# DSP.net
KiCad netlist of a schematic drawn in Altium Designer
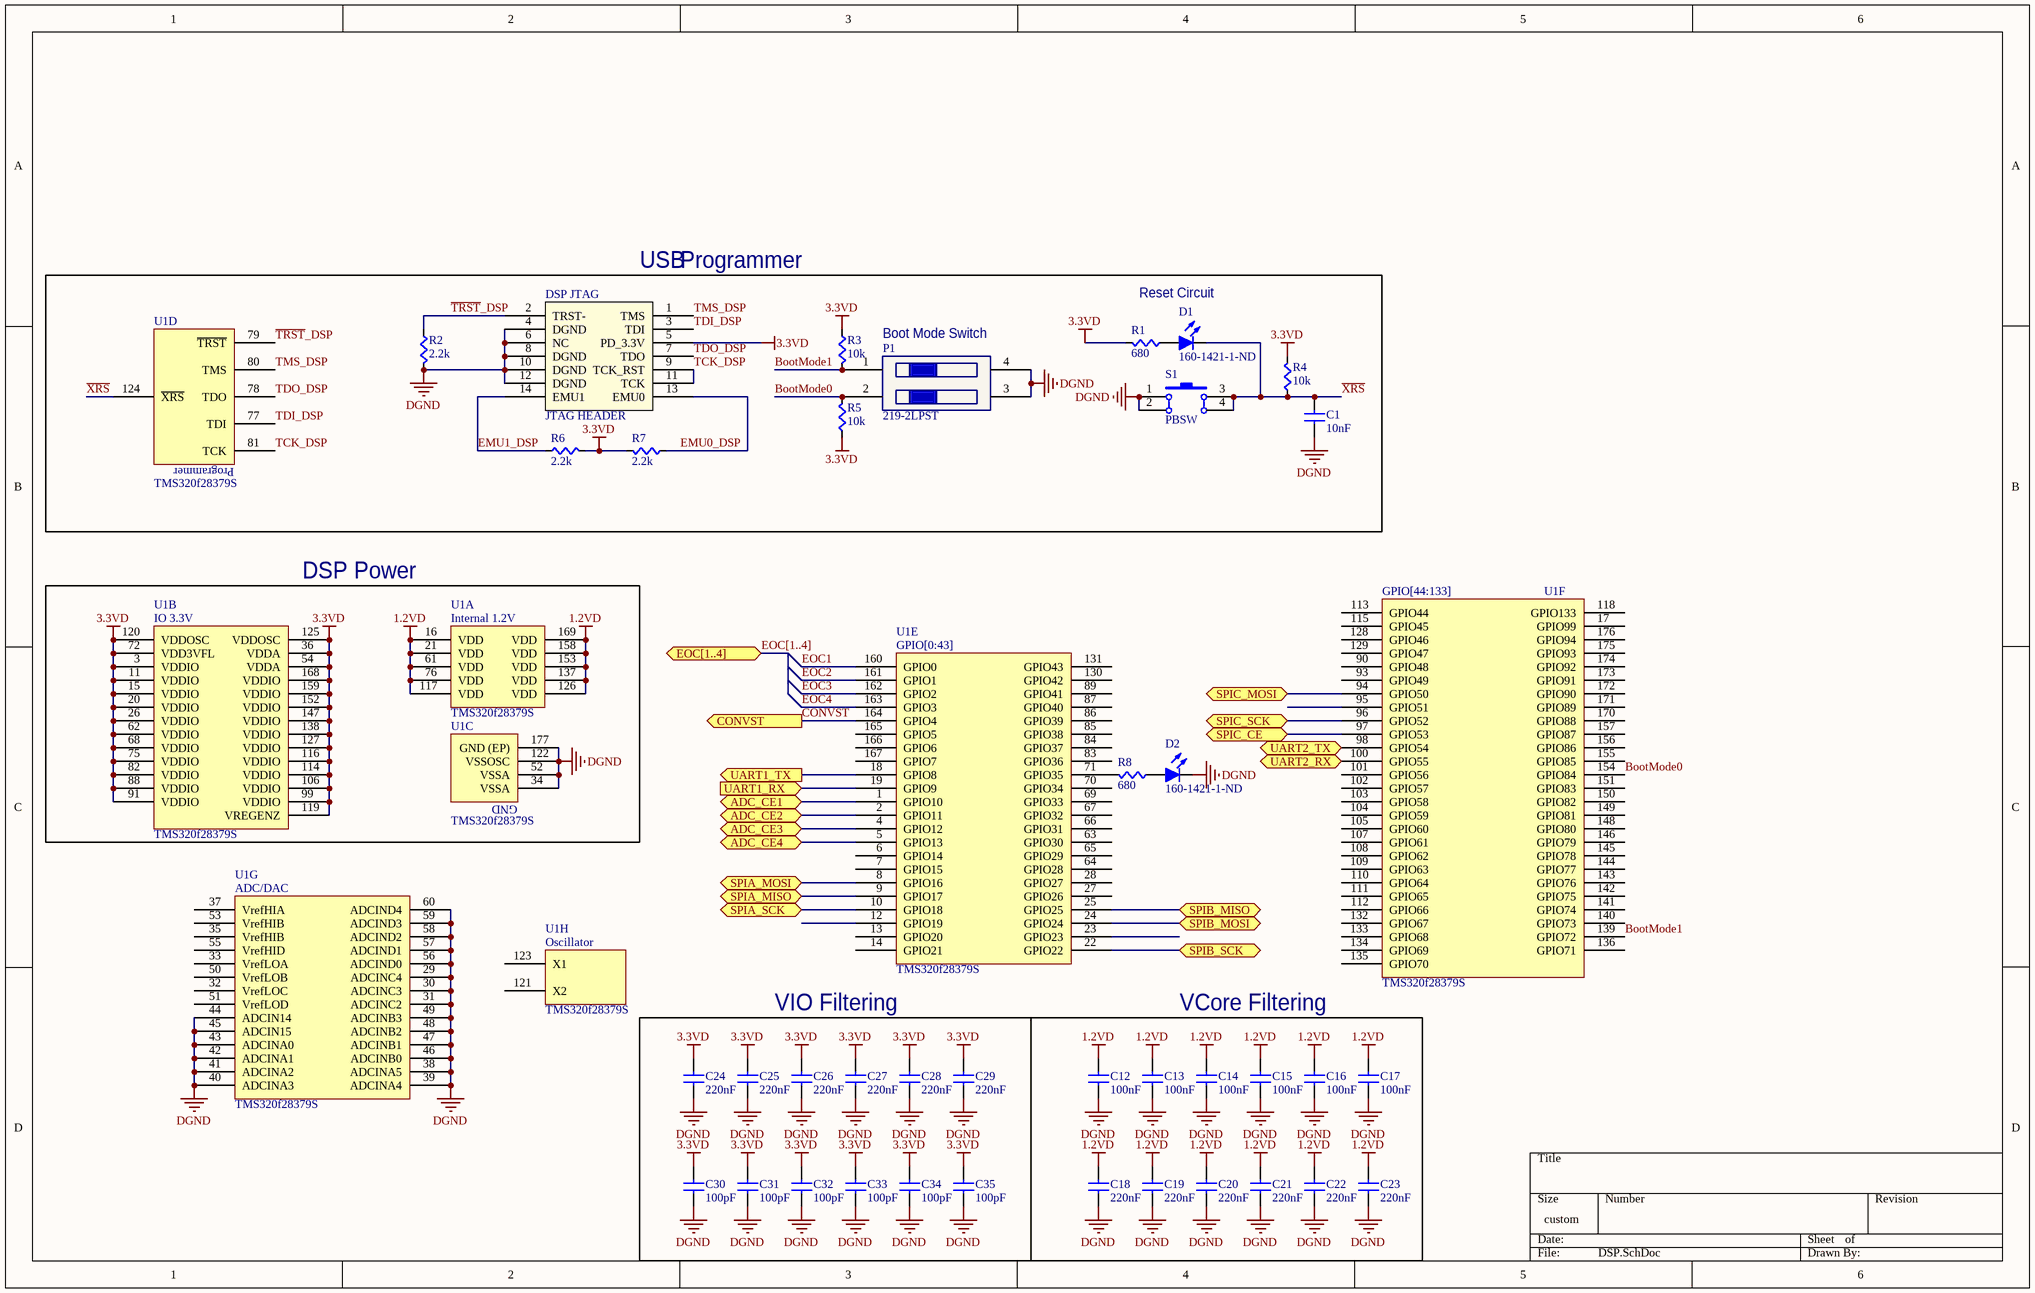
[diagram p0: DSP.SchDoc]

(export (version "E")
  (design (tool "Eeschema 10.0.6"))
  (components
    (comp (ref "C1")
      (value "10nF")
      (footprint "CAPC0603")
      (fields (field (name "Comment") "Cap"))
      (libsource (lib "SubjuGator8") (part "Cap"))
    )
    (comp (ref "C12")
      (value "100nF")
      (footprint "CAPC0603")
      (fields (field (name "Comment") "Cap"))
      (libsource (lib "SubjuGator8") (part "Cap"))
    )
    (comp (ref "C13")
      (value "100nF")
      (footprint "CAPC0603")
      (fields (field (name "Comment") "Cap"))
      (libsource (lib "SubjuGator8") (part "Cap"))
    )
    (comp (ref "C14")
      (value "100nF")
      (footprint "CAPC0603")
      (fields (field (name "Comment") "Cap"))
      (libsource (lib "SubjuGator8") (part "Cap"))
    )
    (comp (ref "C15")
      (value "100nF")
      (footprint "CAPC0603")
      (fields (field (name "Comment") "Cap"))
      (libsource (lib "SubjuGator8") (part "Cap"))
    )
    (comp (ref "C16")
      (value "100nF")
      (footprint "CAPC0603")
      (fields (field (name "Comment") "Cap"))
      (libsource (lib "SubjuGator8") (part "Cap"))
    )
    (comp (ref "C17")
      (value "100nF")
      (footprint "CAPC0603")
      (fields (field (name "Comment") "Cap"))
      (libsource (lib "SubjuGator8") (part "Cap"))
    )
    (comp (ref "C18")
      (value "220nF")
      (footprint "CAPC0603")
      (fields (field (name "Comment") "Cap"))
      (libsource (lib "SubjuGator8") (part "Cap"))
    )
    (comp (ref "C19")
      (value "220nF")
      (footprint "CAPC0603")
      (fields (field (name "Comment") "Cap"))
      (libsource (lib "SubjuGator8") (part "Cap"))
    )
    (comp (ref "C20")
      (value "220nF")
      (footprint "CAPC0603")
      (fields (field (name "Comment") "Cap"))
      (libsource (lib "SubjuGator8") (part "Cap"))
    )
    (comp (ref "C21")
      (value "220nF")
      (footprint "CAPC0603")
      (fields (field (name "Comment") "Cap"))
      (libsource (lib "SubjuGator8") (part "Cap"))
    )
    (comp (ref "C22")
      (value "220nF")
      (footprint "CAPC0603")
      (fields (field (name "Comment") "Cap"))
      (libsource (lib "SubjuGator8") (part "Cap"))
    )
    (comp (ref "C23")
      (value "220nF")
      (footprint "CAPC0603")
      (fields (field (name "Comment") "Cap"))
      (libsource (lib "SubjuGator8") (part "Cap"))
    )
    (comp (ref "C24")
      (value "220nF")
      (footprint "CAPC0603")
      (fields (field (name "Comment") "Cap"))
      (libsource (lib "SubjuGator8") (part "Cap"))
    )
    (comp (ref "C25")
      (value "220nF")
      (footprint "CAPC0603")
      (fields (field (name "Comment") "Cap"))
      (libsource (lib "SubjuGator8") (part "Cap"))
    )
    (comp (ref "C26")
      (value "220nF")
      (footprint "CAPC0603")
      (fields (field (name "Comment") "Cap"))
      (libsource (lib "SubjuGator8") (part "Cap"))
    )
    (comp (ref "C27")
      (value "220nF")
      (footprint "CAPC0603")
      (fields (field (name "Comment") "Cap"))
      (libsource (lib "SubjuGator8") (part "Cap"))
    )
    (comp (ref "C28")
      (value "220nF")
      (footprint "CAPC0603")
      (fields (field (name "Comment") "Cap"))
      (libsource (lib "SubjuGator8") (part "Cap"))
    )
    (comp (ref "C29")
      (value "220nF")
      (footprint "CAPC0603")
      (fields (field (name "Comment") "Cap"))
      (libsource (lib "SubjuGator8") (part "Cap"))
    )
    (comp (ref "C30")
      (value "100pF")
      (footprint "CAPC0603")
      (fields (field (name "Comment") "Cap"))
      (libsource (lib "SubjuGator8") (part "Cap"))
    )
    (comp (ref "C31")
      (value "100pF")
      (footprint "CAPC0603")
      (fields (field (name "Comment") "Cap"))
      (libsource (lib "SubjuGator8") (part "Cap"))
    )
    (comp (ref "C32")
      (value "100pF")
      (footprint "CAPC0603")
      (fields (field (name "Comment") "Cap"))
      (libsource (lib "SubjuGator8") (part "Cap"))
    )
    (comp (ref "C33")
      (value "100pF")
      (footprint "CAPC0603")
      (fields (field (name "Comment") "Cap"))
      (libsource (lib "SubjuGator8") (part "Cap"))
    )
    (comp (ref "C34")
      (value "100pF")
      (footprint "CAPC0603")
      (fields (field (name "Comment") "Cap"))
      (libsource (lib "SubjuGator8") (part "Cap"))
    )
    (comp (ref "C35")
      (value "100pF")
      (footprint "CAPC0603")
      (fields (field (name "Comment") "Cap"))
      (libsource (lib "SubjuGator8") (part "Cap"))
    )
    (comp (ref "D1")
      (value "LED-RED")
      (footprint "Hydrophone:LED0805-RED")
      (description "Light Emitting Diode - RED")
      (fields
        (field (name "MANUFACTURER PART NUMBER") "LTST-C171CKT")
        (field (name "MANUFACTURER") "Lite-On Inc")
        (field (name "SUPPLIER PART NUMBER 1") "160-1421-1-ND")
      )
      (libsource (lib "Hydrophone") (part "LED-RED"))
    )
    (comp (ref "D2")
      (value "LED-RED")
      (footprint "Hydrophone:LED0805-RED")
      (description "Light Emitting Diode - RED")
      (fields
        (field (name "MANUFACTURER PART NUMBER") "LTST-C171CKT")
        (field (name "MANUFACTURER") "Lite-On Inc")
        (field (name "SUPPLIER PART NUMBER") "160-1421-1-ND")
      )
      (libsource (lib "Hydrophone") (part "LED-RED"))
    )
    (comp (ref "DSP JTAG")
      (value "JTAG HEADER")
      (footprint "Hydrophone:JTAG HEADER - 14")
      (description "14 Pin JTAG Header")
      (libsource (lib "Hydrophone") (part "JTAG-TI_14"))
    )
    (comp (ref "P1")
      (value "219-2LPST")
      (footprint "SPST-4N")
      (description "SWITCH TAPE SEAL 2 POS SMD 50V")
      (libsource (lib "SubjuGator8") (part "SPST-2DIP-SW"))
    )
    (comp (ref "R1")
      (value "680")
      (footprint "RES0603")
      (fields (field (name "Comment") "Res"))
      (libsource (lib "SubjuGator8") (part "Res"))
    )
    (comp (ref "R2")
      (value "2.2k")
      (footprint "RES0603")
      (fields (field (name "Comment") "Res"))
      (libsource (lib "SubjuGator8") (part "Res"))
    )
    (comp (ref "R3")
      (value "10k")
      (footprint "RES0603")
      (fields (field (name "Comment") "Res"))
      (libsource (lib "SubjuGator8") (part "Res"))
    )
    (comp (ref "R4")
      (value "10k")
      (footprint "RES0603")
      (fields (field (name "Comment") "Res"))
      (libsource (lib "Passives") (part "Res"))
    )
    (comp (ref "R5")
      (value "10k")
      (footprint "RES0603")
      (fields (field (name "Comment") "Res"))
      (libsource (lib "SubjuGator8") (part "Res"))
    )
    (comp (ref "R6")
      (value "2.2k")
      (footprint "RES0603")
      (fields (field (name "Comment") "Res"))
      (libsource (lib "SubjuGator8") (part "Res"))
    )
    (comp (ref "R7")
      (value "2.2k")
      (footprint "RES0603")
      (fields (field (name "Comment") "Res"))
      (libsource (lib "SubjuGator8") (part "Res"))
    )
    (comp (ref "R8")
      (value "680")
      (footprint "RES0603")
      (fields (field (name "Comment") "Res"))
      (libsource (lib "SubjuGator8") (part "Res"))
    )
    (comp (ref "S1")
      (value "PBSW")
      (footprint "Hydrophone:PBSW")
      (description "Push Button Switch")
      (fields
        (field (name "MANUFACTURER") "Panasonic Electronic Components")
        (field (name "MANUFACTURER PART NUMBER") "EVQ-9P105M")
        (field (name "PUBLISHER") "Altium Limited")
      )
      (libsource (lib "Hydrophone") (part "SW-PB"))
    )
    (comp (ref "U1")
      (value "TMS320f28379S")
      (footprint "PQFP-177N")
      (description "IC MCU 200MHZ FPU DSP")
      (libsource (lib "ICs") (part "TMS320f28379S"))
    )
  )
  (nets
    (net (code "1") (name "/ADC_CE1") (class "Default")
      (node (ref "U1") (pin "1") (pinfunction "GPIO10_1") (pintype "passive"))
    )
    (net (code "2") (name "/ADC_CE2") (class "Default")
      (node (ref "U1") (pin "2") (pinfunction "GPIO11_2") (pintype "passive"))
    )
    (net (code "3") (name "/ADC_CE3") (class "Default")
      (node (ref "U1") (pin "4") (pinfunction "GPIO12_4") (pintype "passive"))
    )
    (net (code "4") (name "/ADC_CE4") (class "Default")
      (node (ref "U1") (pin "5") (pinfunction "GPIO13_5") (pintype "passive"))
    )
    (net (code "5") (name "/BootMode0") (class "Default")
      (node (ref "P1") (pin "2") (pinfunction "2_2") (pintype "passive"))
      (node (ref "R5") (pin "1") (pinfunction "A_1") (pintype "passive"))
      (node (ref "U1") (pin "154") (pinfunction "GPIO84_154") (pintype "passive"))
    )
    (net (code "6") (name "/BootMode1") (class "Default")
      (node (ref "P1") (pin "1") (pinfunction "1_1") (pintype "passive"))
      (node (ref "R3") (pin "1") (pinfunction "A_1") (pintype "passive"))
      (node (ref "U1") (pin "139") (pinfunction "GPIO72_139") (pintype "passive"))
    )
    (net (code "7") (name "/CONVST") (class "Default")
      (node (ref "U1") (pin "164") (pinfunction "GPIO4_164") (pintype "passive"))
    )
    (net (code "8") (name "/EMU0_DSP") (class "Default")
      (node (ref "DSP JTAG") (pin "13") (pinfunction "EMU0_13") (pintype "passive"))
      (node (ref "R7") (pin "2") (pinfunction "B_2") (pintype "passive"))
    )
    (net (code "9") (name "/EMU1_DSP") (class "Default")
      (node (ref "DSP JTAG") (pin "14") (pinfunction "EMU1_14") (pintype "passive"))
      (node (ref "R6") (pin "2") (pinfunction "B_2") (pintype "passive"))
    )
    (net (code "10") (name "/EOC1") (class "Default")
      (node (ref "U1") (pin "160") (pinfunction "GPIO0_160") (pintype "passive"))
    )
    (net (code "11") (name "/EOC2") (class "Default")
      (node (ref "U1") (pin "161") (pinfunction "GPIO1_161") (pintype "passive"))
    )
    (net (code "12") (name "/EOC3") (class "Default")
      (node (ref "U1") (pin "162") (pinfunction "GPIO2_162") (pintype "passive"))
    )
    (net (code "13") (name "/EOC4") (class "Default")
      (node (ref "U1") (pin "163") (pinfunction "GPIO3_163") (pintype "passive"))
    )
    (net (code "15") (name "/SPIA_MISO") (class "Default")
      (node (ref "U1") (pin "9") (pinfunction "GPIO17_9") (pintype "passive"))
    )
    (net (code "16") (name "/SPIA_MOSI") (class "Default")
      (node (ref "U1") (pin "8") (pinfunction "GPIO16_8") (pintype "passive"))
    )
    (net (code "17") (name "/SPIA_SCK") (class "Default")
      (node (ref "U1") (pin "10") (pinfunction "GPIO18_10") (pintype "passive"))
    )
    (net (code "18") (name "/SPIB_MISO") (class "Default")
      (node (ref "U1") (pin "25") (pinfunction "GPIO25_25") (pintype "passive"))
    )
    (net (code "19") (name "/SPIB_MOSI") (class "Default")
      (node (ref "U1") (pin "24") (pinfunction "GPIO24_24") (pintype "passive"))
    )
    (net (code "20") (name "/SPIB_SCK") (class "Default")
      (node (ref "U1") (pin "22") (pinfunction "GPIO22_22") (pintype "passive"))
    )
    (net (code "21") (name "/SPIC_CE") (class "Default")
      (node (ref "U1") (pin "97") (pinfunction "GPIO53_97") (pintype "passive"))
    )
    (net (code "22") (name "/SPIC_MOSI") (class "Default")
      (node (ref "U1") (pin "94") (pinfunction "GPIO50_94") (pintype "passive"))
    )
    (net (code "23") (name "/SPIC_SCK") (class "Default")
      (node (ref "U1") (pin "96") (pinfunction "GPIO52_96") (pintype "passive"))
    )
    (net (code "24") (name "/TCK_DSP") (class "Default")
      (node (ref "DSP JTAG") (pin "11") (pinfunction "TCK_11") (pintype "passive"))
      (node (ref "DSP JTAG") (pin "9") (pinfunction "TCK_RST_9") (pintype "passive"))
      (node (ref "U1") (pin "81") (pinfunction "TCK_81") (pintype "passive"))
    )
    (net (code "25") (name "/TDI_DSP") (class "Default")
      (node (ref "DSP JTAG") (pin "3") (pinfunction "TDI_3") (pintype "passive"))
      (node (ref "U1") (pin "77") (pinfunction "TDI_77") (pintype "passive"))
    )
    (net (code "26") (name "/TDO_DSP") (class "Default")
      (node (ref "DSP JTAG") (pin "7") (pinfunction "TDO_7") (pintype "passive"))
      (node (ref "U1") (pin "78") (pinfunction "TDO_78") (pintype "passive"))
    )
    (net (code "27") (name "/TMS_DSP") (class "Default")
      (node (ref "DSP JTAG") (pin "1") (pinfunction "TMS_1") (pintype "passive"))
      (node (ref "U1") (pin "80") (pinfunction "TMS_80") (pintype "passive"))
    )
    (net (code "28") (name "/UART1_RX") (class "Default")
      (node (ref "U1") (pin "19") (pinfunction "GPIO9_19") (pintype "passive"))
    )
    (net (code "29") (name "/UART1_TX") (class "Default")
      (node (ref "U1") (pin "18") (pinfunction "GPIO8_18") (pintype "passive"))
    )
    (net (code "30") (name "/UART2_RX") (class "Default")
      (node (ref "U1") (pin "100") (pinfunction "GPIO55_100") (pintype "passive"))
    )
    (net (code "31") (name "/UART2_TX") (class "Default")
      (node (ref "U1") (pin "98") (pinfunction "GPIO54_98") (pintype "passive"))
    )
    (net (code "32") (name "/~{TRST}_DSP") (class "Default")
      (node (ref "DSP JTAG") (pin "2") (pinfunction "TRST-_2") (pintype "passive"))
      (node (ref "R2") (pin "2") (pinfunction "B_2") (pintype "passive"))
      (node (ref "U1") (pin "79") (pinfunction "~{TRST}_79") (pintype "passive"))
    )
    (net (code "33") (name "/~{XRS}") (class "Default")
      (node (ref "C1") (pin "1") (pinfunction "A_1") (pintype "passive"))
      (node (ref "D1") (pin "1") (pinfunction "K_1") (pintype "passive"))
      (node (ref "R4") (pin "2") (pinfunction "B_2") (pintype "passive"))
      (node (ref "S1") (pin "3") (pinfunction "B_3") (pintype "passive"))
      (node (ref "S1") (pin "4") (pinfunction "B'_4") (pintype "passive"))
      (node (ref "U1") (pin "124") (pinfunction "~{XRS}_124") (pintype "passive"))
    )
    (net (code "34") (name "1.2VD") (class "Default")
      (node (ref "C12") (pin "1") (pinfunction "A_1") (pintype "passive"))
      (node (ref "C13") (pin "1") (pinfunction "A_1") (pintype "passive"))
      (node (ref "C14") (pin "1") (pinfunction "A_1") (pintype "passive"))
      (node (ref "C15") (pin "1") (pinfunction "A_1") (pintype "passive"))
      (node (ref "C16") (pin "1") (pinfunction "A_1") (pintype "passive"))
      (node (ref "C17") (pin "1") (pinfunction "A_1") (pintype "passive"))
      (node (ref "C18") (pin "1") (pinfunction "A_1") (pintype "passive"))
      (node (ref "C19") (pin "1") (pinfunction "A_1") (pintype "passive"))
      (node (ref "C20") (pin "1") (pinfunction "A_1") (pintype "passive"))
      (node (ref "C21") (pin "1") (pinfunction "A_1") (pintype "passive"))
      (node (ref "C22") (pin "1") (pinfunction "A_1") (pintype "passive"))
      (node (ref "C23") (pin "1") (pinfunction "A_1") (pintype "passive"))
      (node (ref "U1") (pin "117") (pinfunction "VDD_117") (pintype "passive"))
      (node (ref "U1") (pin "126") (pinfunction "VDD_126") (pintype "passive"))
      (node (ref "U1") (pin "137") (pinfunction "VDD_137") (pintype "passive"))
      (node (ref "U1") (pin "153") (pinfunction "VDD_153") (pintype "passive"))
      (node (ref "U1") (pin "158") (pinfunction "VDD_158") (pintype "passive"))
      (node (ref "U1") (pin "16") (pinfunction "VDD_16") (pintype "passive"))
      (node (ref "U1") (pin "169") (pinfunction "VDD_169") (pintype "passive"))
      (node (ref "U1") (pin "21") (pinfunction "VDD_21") (pintype "passive"))
      (node (ref "U1") (pin "61") (pinfunction "VDD_61") (pintype "passive"))
      (node (ref "U1") (pin "76") (pinfunction "VDD_76") (pintype "passive"))
    )
    (net (code "35") (name "3.3VD") (class "Default")
      (node (ref "C24") (pin "1") (pinfunction "A_1") (pintype "passive"))
      (node (ref "C25") (pin "1") (pinfunction "A_1") (pintype "passive"))
      (node (ref "C26") (pin "1") (pinfunction "A_1") (pintype "passive"))
      (node (ref "C27") (pin "1") (pinfunction "A_1") (pintype "passive"))
      (node (ref "C28") (pin "1") (pinfunction "A_1") (pintype "passive"))
      (node (ref "C29") (pin "1") (pinfunction "A_1") (pintype "passive"))
      (node (ref "C30") (pin "1") (pinfunction "A_1") (pintype "passive"))
      (node (ref "C31") (pin "1") (pinfunction "A_1") (pintype "passive"))
      (node (ref "C32") (pin "1") (pinfunction "A_1") (pintype "passive"))
      (node (ref "C33") (pin "1") (pinfunction "A_1") (pintype "passive"))
      (node (ref "C34") (pin "1") (pinfunction "A_1") (pintype "passive"))
      (node (ref "C35") (pin "1") (pinfunction "A_1") (pintype "passive"))
      (node (ref "DSP JTAG") (pin "5") (pinfunction "PD_3.3V_5") (pintype "passive"))
      (node (ref "R1") (pin "1") (pinfunction "A_1") (pintype "passive"))
      (node (ref "R3") (pin "2") (pinfunction "B_2") (pintype "passive"))
      (node (ref "R4") (pin "1") (pinfunction "A_1") (pintype "passive"))
      (node (ref "R5") (pin "2") (pinfunction "B_2") (pintype "passive"))
      (node (ref "R6") (pin "1") (pinfunction "A_1") (pintype "passive"))
      (node (ref "R7") (pin "1") (pinfunction "A_1") (pintype "passive"))
      (node (ref "U1") (pin "106") (pinfunction "VDDIO_106") (pintype "passive"))
      (node (ref "U1") (pin "11") (pinfunction "VDDIO_11") (pintype "passive"))
      (node (ref "U1") (pin "114") (pinfunction "VDDIO_114") (pintype "passive"))
      (node (ref "U1") (pin "116") (pinfunction "VDDIO_116") (pintype "passive"))
      (node (ref "U1") (pin "119") (pinfunction "VREGENZ_119") (pintype "passive"))
      (node (ref "U1") (pin "120") (pinfunction "VDDOSC_120") (pintype "passive"))
      (node (ref "U1") (pin "125") (pinfunction "VDDOSC_125") (pintype "passive"))
      (node (ref "U1") (pin "127") (pinfunction "VDDIO_127") (pintype "passive"))
      (node (ref "U1") (pin "138") (pinfunction "VDDIO_138") (pintype "passive"))
      (node (ref "U1") (pin "147") (pinfunction "VDDIO_147") (pintype "passive"))
      (node (ref "U1") (pin "15") (pinfunction "VDDIO_15") (pintype "passive"))
      (node (ref "U1") (pin "152") (pinfunction "VDDIO_152") (pintype "passive"))
      (node (ref "U1") (pin "159") (pinfunction "VDDIO_159") (pintype "passive"))
      (node (ref "U1") (pin "168") (pinfunction "VDDIO_168") (pintype "passive"))
      (node (ref "U1") (pin "20") (pinfunction "VDDIO_20") (pintype "passive"))
      (node (ref "U1") (pin "26") (pinfunction "VDDIO_26") (pintype "passive"))
      (node (ref "U1") (pin "3") (pinfunction "VDDIO_3") (pintype "passive"))
      (node (ref "U1") (pin "36") (pinfunction "VDDA_36") (pintype "passive"))
      (node (ref "U1") (pin "54") (pinfunction "VDDA_54") (pintype "passive"))
      (node (ref "U1") (pin "62") (pinfunction "VDDIO_62") (pintype "passive"))
      (node (ref "U1") (pin "68") (pinfunction "VDDIO_68") (pintype "passive"))
      (node (ref "U1") (pin "72") (pinfunction "VDD3VFL_72") (pintype "passive"))
      (node (ref "U1") (pin "75") (pinfunction "VDDIO_75") (pintype "passive"))
      (node (ref "U1") (pin "82") (pinfunction "VDDIO_82") (pintype "passive"))
      (node (ref "U1") (pin "88") (pinfunction "VDDIO_88") (pintype "passive"))
      (node (ref "U1") (pin "91") (pinfunction "VDDIO_91") (pintype "passive"))
      (node (ref "U1") (pin "99") (pinfunction "VDDIO_99") (pintype "passive"))
    )
    (net (code "36") (name "DGND") (class "Default")
      (node (ref "C1") (pin "2") (pinfunction "B_2") (pintype "passive"))
      (node (ref "C12") (pin "2") (pinfunction "B_2") (pintype "passive"))
      (node (ref "C13") (pin "2") (pinfunction "B_2") (pintype "passive"))
      (node (ref "C14") (pin "2") (pinfunction "B_2") (pintype "passive"))
      (node (ref "C15") (pin "2") (pinfunction "B_2") (pintype "passive"))
      (node (ref "C16") (pin "2") (pinfunction "B_2") (pintype "passive"))
      (node (ref "C17") (pin "2") (pinfunction "B_2") (pintype "passive"))
      (node (ref "C18") (pin "2") (pinfunction "B_2") (pintype "passive"))
      (node (ref "C19") (pin "2") (pinfunction "B_2") (pintype "passive"))
      (node (ref "C20") (pin "2") (pinfunction "B_2") (pintype "passive"))
      (node (ref "C21") (pin "2") (pinfunction "B_2") (pintype "passive"))
      (node (ref "C22") (pin "2") (pinfunction "B_2") (pintype "passive"))
      (node (ref "C23") (pin "2") (pinfunction "B_2") (pintype "passive"))
      (node (ref "C24") (pin "2") (pinfunction "B_2") (pintype "passive"))
      (node (ref "C25") (pin "2") (pinfunction "B_2") (pintype "passive"))
      (node (ref "C26") (pin "2") (pinfunction "B_2") (pintype "passive"))
      (node (ref "C27") (pin "2") (pinfunction "B_2") (pintype "passive"))
      (node (ref "C28") (pin "2") (pinfunction "B_2") (pintype "passive"))
      (node (ref "C29") (pin "2") (pinfunction "B_2") (pintype "passive"))
      (node (ref "C30") (pin "2") (pinfunction "B_2") (pintype "passive"))
      (node (ref "C31") (pin "2") (pinfunction "B_2") (pintype "passive"))
      (node (ref "C32") (pin "2") (pinfunction "B_2") (pintype "passive"))
      (node (ref "C33") (pin "2") (pinfunction "B_2") (pintype "passive"))
      (node (ref "C34") (pin "2") (pinfunction "B_2") (pintype "passive"))
      (node (ref "C35") (pin "2") (pinfunction "B_2") (pintype "passive"))
      (node (ref "D2") (pin "1") (pinfunction "K_1") (pintype "passive"))
      (node (ref "DSP JTAG") (pin "10") (pinfunction "DGND_10") (pintype "passive"))
      (node (ref "DSP JTAG") (pin "12") (pinfunction "DGND_12") (pintype "passive"))
      (node (ref "DSP JTAG") (pin "4") (pinfunction "DGND_4") (pintype "passive"))
      (node (ref "DSP JTAG") (pin "6") (pinfunction "NC_6") (pintype "passive"))
      (node (ref "DSP JTAG") (pin "8") (pinfunction "DGND_8") (pintype "passive"))
      (node (ref "P1") (pin "3") (pinfunction "3_3") (pintype "passive"))
      (node (ref "P1") (pin "4") (pinfunction "4_4") (pintype "passive"))
      (node (ref "R2") (pin "1") (pinfunction "A_1") (pintype "passive"))
      (node (ref "S1") (pin "1") (pinfunction "A_1") (pintype "passive"))
      (node (ref "S1") (pin "2") (pinfunction "A'_2") (pintype "passive"))
      (node (ref "U1") (pin "122") (pinfunction "VSSOSC_122") (pintype "passive"))
      (node (ref "U1") (pin "177") (pinfunction "GND_(EP)_177") (pintype "passive"))
      (node (ref "U1") (pin "29") (pinfunction "ADCINC4_29") (pintype "passive"))
      (node (ref "U1") (pin "30") (pinfunction "ADCINC3_30") (pintype "passive"))
      (node (ref "U1") (pin "31") (pinfunction "ADCINC2_31") (pintype "passive"))
      (node (ref "U1") (pin "34") (pinfunction "VSSA_34") (pintype "passive"))
      (node (ref "U1") (pin "38") (pinfunction "ADCINA5_38") (pintype "passive"))
      (node (ref "U1") (pin "39") (pinfunction "ADCINA4_39") (pintype "passive"))
      (node (ref "U1") (pin "40") (pinfunction "ADCINA3_40") (pintype "passive"))
      (node (ref "U1") (pin "41") (pinfunction "ADCINA2_41") (pintype "passive"))
      (node (ref "U1") (pin "42") (pinfunction "ADCINA1_42") (pintype "passive"))
      (node (ref "U1") (pin "43") (pinfunction "ADCINA0_43") (pintype "passive"))
      (node (ref "U1") (pin "44") (pinfunction "ADCIN14_44") (pintype "passive"))
      (node (ref "U1") (pin "45") (pinfunction "ADCIN15_45") (pintype "passive"))
      (node (ref "U1") (pin "46") (pinfunction "ADCINB0_46") (pintype "passive"))
      (node (ref "U1") (pin "47") (pinfunction "ADCINB1_47") (pintype "passive"))
      (node (ref "U1") (pin "48") (pinfunction "ADCINB2_48") (pintype "passive"))
      (node (ref "U1") (pin "49") (pinfunction "ADCINB3_49") (pintype "passive"))
      (node (ref "U1") (pin "52") (pinfunction "VSSA_52") (pintype "passive"))
      (node (ref "U1") (pin "56") (pinfunction "ADCIND0_56") (pintype "passive"))
      (node (ref "U1") (pin "57") (pinfunction "ADCIND1_57") (pintype "passive"))
      (node (ref "U1") (pin "58") (pinfunction "ADCIND2_58") (pintype "passive"))
      (node (ref "U1") (pin "59") (pinfunction "ADCIND3_59") (pintype "passive"))
      (node (ref "U1") (pin "60") (pinfunction "ADCIND4_60") (pintype "passive"))
    )
    (net (code "37") (name "Net-(D1-A)") (class "Default")
      (node (ref "D1") (pin "2") (pinfunction "A_2") (pintype "passive"))
      (node (ref "R1") (pin "2") (pinfunction "B_2") (pintype "passive"))
    )
    (net (code "38") (name "Net-(D2-A)") (class "Default")
      (node (ref "D2") (pin "2") (pinfunction "A_2") (pintype "passive"))
      (node (ref "R8") (pin "2") (pinfunction "B_2") (pintype "passive"))
    )
    (net (code "39") (name "Net-(R8-A)") (class "Default")
      (node (ref "R8") (pin "1") (pinfunction "A_1") (pintype "passive"))
      (node (ref "U1") (pin "71") (pinfunction "GPIO35_71") (pintype "passive"))
    )
    (net (code "40") (name "unconnected-(U1E-GPIO5-Pad165)") (class "Default")
      (node (ref "U1") (pin "165") (pinfunction "GPIO5_165") (pintype "passive"))
    )
    (net (code "41") (name "unconnected-(U1E-GPIO6-Pad166)") (class "Default")
      (node (ref "U1") (pin "166") (pinfunction "GPIO6_166") (pintype "passive"))
    )
    (net (code "42") (name "unconnected-(U1E-GPIO7-Pad167)") (class "Default")
      (node (ref "U1") (pin "167") (pinfunction "GPIO7_167") (pintype "passive"))
    )
    (net (code "43") (name "unconnected-(U1E-GPIO14-Pad6)") (class "Default")
      (node (ref "U1") (pin "6") (pinfunction "GPIO14_6") (pintype "passive"))
    )
    (net (code "44") (name "unconnected-(U1E-GPIO15-Pad7)") (class "Default")
      (node (ref "U1") (pin "7") (pinfunction "GPIO15_7") (pintype "passive"))
    )
    (net (code "45") (name "unconnected-(U1E-GPIO19-Pad12)") (class "Default")
      (node (ref "U1") (pin "12") (pinfunction "GPIO19_12") (pintype "passive"))
    )
    (net (code "46") (name "unconnected-(U1E-GPIO20-Pad13)") (class "Default")
      (node (ref "U1") (pin "13") (pinfunction "GPIO20_13") (pintype "passive"))
    )
    (net (code "47") (name "unconnected-(U1E-GPIO21-Pad14)") (class "Default")
      (node (ref "U1") (pin "14") (pinfunction "GPIO21_14") (pintype "passive"))
    )
    (net (code "48") (name "unconnected-(U1E-GPIO23-Pad23)") (class "Default")
      (node (ref "U1") (pin "23") (pinfunction "GPIO23_23") (pintype "passive"))
    )
    (net (code "49") (name "unconnected-(U1E-GPIO26-Pad27)") (class "Default")
      (node (ref "U1") (pin "27") (pinfunction "GPIO26_27") (pintype "passive"))
    )
    (net (code "50") (name "unconnected-(U1E-GPIO27-Pad28)") (class "Default")
      (node (ref "U1") (pin "28") (pinfunction "GPIO27_28") (pintype "passive"))
    )
    (net (code "51") (name "unconnected-(U1E-GPIO28-Pad64)") (class "Default")
      (node (ref "U1") (pin "64") (pinfunction "GPIO28_64") (pintype "passive"))
    )
    (net (code "52") (name "unconnected-(U1E-GPIO29-Pad65)") (class "Default")
      (node (ref "U1") (pin "65") (pinfunction "GPIO29_65") (pintype "passive"))
    )
    (net (code "53") (name "unconnected-(U1E-GPIO30-Pad63)") (class "Default")
      (node (ref "U1") (pin "63") (pinfunction "GPIO30_63") (pintype "passive"))
    )
    (net (code "54") (name "unconnected-(U1E-GPIO31-Pad66)") (class "Default")
      (node (ref "U1") (pin "66") (pinfunction "GPIO31_66") (pintype "passive"))
    )
    (net (code "55") (name "unconnected-(U1E-GPIO32-Pad67)") (class "Default")
      (node (ref "U1") (pin "67") (pinfunction "GPIO32_67") (pintype "passive"))
    )
    (net (code "56") (name "unconnected-(U1E-GPIO33-Pad69)") (class "Default")
      (node (ref "U1") (pin "69") (pinfunction "GPIO33_69") (pintype "passive"))
    )
    (net (code "57") (name "unconnected-(U1E-GPIO34-Pad70)") (class "Default")
      (node (ref "U1") (pin "70") (pinfunction "GPIO34_70") (pintype "passive"))
    )
    (net (code "58") (name "unconnected-(U1E-GPIO36-Pad83)") (class "Default")
      (node (ref "U1") (pin "83") (pinfunction "GPIO36_83") (pintype "passive"))
    )
    (net (code "59") (name "unconnected-(U1E-GPIO37-Pad84)") (class "Default")
      (node (ref "U1") (pin "84") (pinfunction "GPIO37_84") (pintype "passive"))
    )
    (net (code "60") (name "unconnected-(U1E-GPIO38-Pad85)") (class "Default")
      (node (ref "U1") (pin "85") (pinfunction "GPIO38_85") (pintype "passive"))
    )
    (net (code "61") (name "unconnected-(U1E-GPIO39-Pad86)") (class "Default")
      (node (ref "U1") (pin "86") (pinfunction "GPIO39_86") (pintype "passive"))
    )
    (net (code "62") (name "unconnected-(U1E-GPIO40-Pad87)") (class "Default")
      (node (ref "U1") (pin "87") (pinfunction "GPIO40_87") (pintype "passive"))
    )
    (net (code "63") (name "unconnected-(U1E-GPIO41-Pad89)") (class "Default")
      (node (ref "U1") (pin "89") (pinfunction "GPIO41_89") (pintype "passive"))
    )
    (net (code "64") (name "unconnected-(U1E-GPIO42-Pad130)") (class "Default")
      (node (ref "U1") (pin "130") (pinfunction "GPIO42_130") (pintype "passive"))
    )
    (net (code "65") (name "unconnected-(U1E-GPIO43-Pad131)") (class "Default")
      (node (ref "U1") (pin "131") (pinfunction "GPIO43_131") (pintype "passive"))
    )
    (net (code "66") (name "unconnected-(U1F-GPIO44-Pad113)") (class "Default")
      (node (ref "U1") (pin "113") (pinfunction "GPIO44_113") (pintype "passive"))
    )
    (net (code "67") (name "unconnected-(U1F-GPIO45-Pad115)") (class "Default")
      (node (ref "U1") (pin "115") (pinfunction "GPIO45_115") (pintype "passive"))
    )
    (net (code "68") (name "unconnected-(U1F-GPIO46-Pad128)") (class "Default")
      (node (ref "U1") (pin "128") (pinfunction "GPIO46_128") (pintype "passive"))
    )
    (net (code "69") (name "unconnected-(U1F-GPIO47-Pad129)") (class "Default")
      (node (ref "U1") (pin "129") (pinfunction "GPIO47_129") (pintype "passive"))
    )
    (net (code "70") (name "unconnected-(U1F-GPIO48-Pad90)") (class "Default")
      (node (ref "U1") (pin "90") (pinfunction "GPIO48_90") (pintype "passive"))
    )
    (net (code "71") (name "unconnected-(U1F-GPIO49-Pad93)") (class "Default")
      (node (ref "U1") (pin "93") (pinfunction "GPIO49_93") (pintype "passive"))
    )
    (net (code "72") (name "unconnected-(U1F-GPIO51-Pad95)") (class "Default")
      (node (ref "U1") (pin "95") (pinfunction "GPIO51_95") (pintype "passive"))
    )
    (net (code "73") (name "unconnected-(U1F-GPIO56-Pad101)") (class "Default")
      (node (ref "U1") (pin "101") (pinfunction "GPIO56_101") (pintype "passive"))
    )
    (net (code "74") (name "unconnected-(U1F-GPIO57-Pad102)") (class "Default")
      (node (ref "U1") (pin "102") (pinfunction "GPIO57_102") (pintype "passive"))
    )
    (net (code "75") (name "unconnected-(U1F-GPIO58-Pad103)") (class "Default")
      (node (ref "U1") (pin "103") (pinfunction "GPIO58_103") (pintype "passive"))
    )
    (net (code "76") (name "unconnected-(U1F-GPIO59-Pad104)") (class "Default")
      (node (ref "U1") (pin "104") (pinfunction "GPIO59_104") (pintype "passive"))
    )
    (net (code "77") (name "unconnected-(U1F-GPIO60-Pad105)") (class "Default")
      (node (ref "U1") (pin "105") (pinfunction "GPIO60_105") (pintype "passive"))
    )
    (net (code "78") (name "unconnected-(U1F-GPIO61-Pad107)") (class "Default")
      (node (ref "U1") (pin "107") (pinfunction "GPIO61_107") (pintype "passive"))
    )
    (net (code "79") (name "unconnected-(U1F-GPIO62-Pad108)") (class "Default")
      (node (ref "U1") (pin "108") (pinfunction "GPIO62_108") (pintype "passive"))
    )
    (net (code "80") (name "unconnected-(U1F-GPIO63-Pad109)") (class "Default")
      (node (ref "U1") (pin "109") (pinfunction "GPIO63_109") (pintype "passive"))
    )
    (net (code "81") (name "unconnected-(U1F-GPIO64-Pad110)") (class "Default")
      (node (ref "U1") (pin "110") (pinfunction "GPIO64_110") (pintype "passive"))
    )
    (net (code "82") (name "unconnected-(U1F-GPIO65-Pad111)") (class "Default")
      (node (ref "U1") (pin "111") (pinfunction "GPIO65_111") (pintype "passive"))
    )
    (net (code "83") (name "unconnected-(U1F-GPIO66-Pad112)") (class "Default")
      (node (ref "U1") (pin "112") (pinfunction "GPIO66_112") (pintype "passive"))
    )
    (net (code "84") (name "unconnected-(U1F-GPIO67-Pad132)") (class "Default")
      (node (ref "U1") (pin "132") (pinfunction "GPIO67_132") (pintype "passive"))
    )
    (net (code "85") (name "unconnected-(U1F-GPIO68-Pad133)") (class "Default")
      (node (ref "U1") (pin "133") (pinfunction "GPIO68_133") (pintype "passive"))
    )
    (net (code "86") (name "unconnected-(U1F-GPIO69-Pad134)") (class "Default")
      (node (ref "U1") (pin "134") (pinfunction "GPIO69_134") (pintype "passive"))
    )
    (net (code "87") (name "unconnected-(U1F-GPIO70-Pad135)") (class "Default")
      (node (ref "U1") (pin "135") (pinfunction "GPIO70_135") (pintype "passive"))
    )
    (net (code "88") (name "unconnected-(U1F-GPIO71-Pad136)") (class "Default")
      (node (ref "U1") (pin "136") (pinfunction "GPIO71_136") (pintype "passive"))
    )
    (net (code "89") (name "unconnected-(U1F-GPIO73-Pad140)") (class "Default")
      (node (ref "U1") (pin "140") (pinfunction "GPIO73_140") (pintype "passive"))
    )
    (net (code "90") (name "unconnected-(U1F-GPIO74-Pad141)") (class "Default")
      (node (ref "U1") (pin "141") (pinfunction "GPIO74_141") (pintype "passive"))
    )
    (net (code "91") (name "unconnected-(U1F-GPIO75-Pad142)") (class "Default")
      (node (ref "U1") (pin "142") (pinfunction "GPIO75_142") (pintype "passive"))
    )
    (net (code "92") (name "unconnected-(U1F-GPIO76-Pad143)") (class "Default")
      (node (ref "U1") (pin "143") (pinfunction "GPIO76_143") (pintype "passive"))
    )
    (net (code "93") (name "unconnected-(U1F-GPIO77-Pad144)") (class "Default")
      (node (ref "U1") (pin "144") (pinfunction "GPIO77_144") (pintype "passive"))
    )
    (net (code "94") (name "unconnected-(U1F-GPIO78-Pad145)") (class "Default")
      (node (ref "U1") (pin "145") (pinfunction "GPIO78_145") (pintype "passive"))
    )
    (net (code "95") (name "unconnected-(U1F-GPIO79-Pad146)") (class "Default")
      (node (ref "U1") (pin "146") (pinfunction "GPIO79_146") (pintype "passive"))
    )
    (net (code "96") (name "unconnected-(U1F-GPIO80-Pad148)") (class "Default")
      (node (ref "U1") (pin "148") (pinfunction "GPIO80_148") (pintype "passive"))
    )
    (net (code "97") (name "unconnected-(U1F-GPIO81-Pad149)") (class "Default")
      (node (ref "U1") (pin "149") (pinfunction "GPIO81_149") (pintype "passive"))
    )
    (net (code "98") (name "unconnected-(U1F-GPIO82-Pad150)") (class "Default")
      (node (ref "U1") (pin "150") (pinfunction "GPIO82_150") (pintype "passive"))
    )
    (net (code "99") (name "unconnected-(U1F-GPIO83-Pad151)") (class "Default")
      (node (ref "U1") (pin "151") (pinfunction "GPIO83_151") (pintype "passive"))
    )
    (net (code "100") (name "unconnected-(U1F-GPIO85-Pad155)") (class "Default")
      (node (ref "U1") (pin "155") (pinfunction "GPIO85_155") (pintype "passive"))
    )
    (net (code "101") (name "unconnected-(U1F-GPIO86-Pad156)") (class "Default")
      (node (ref "U1") (pin "156") (pinfunction "GPIO86_156") (pintype "passive"))
    )
    (net (code "102") (name "unconnected-(U1F-GPIO87-Pad157)") (class "Default")
      (node (ref "U1") (pin "157") (pinfunction "GPIO87_157") (pintype "passive"))
    )
    (net (code "103") (name "unconnected-(U1F-GPIO88-Pad170)") (class "Default")
      (node (ref "U1") (pin "170") (pinfunction "GPIO88_170") (pintype "passive"))
    )
    (net (code "104") (name "unconnected-(U1F-GPIO89-Pad171)") (class "Default")
      (node (ref "U1") (pin "171") (pinfunction "GPIO89_171") (pintype "passive"))
    )
    (net (code "105") (name "unconnected-(U1F-GPIO90-Pad172)") (class "Default")
      (node (ref "U1") (pin "172") (pinfunction "GPIO90_172") (pintype "passive"))
    )
    (net (code "106") (name "unconnected-(U1F-GPIO91-Pad173)") (class "Default")
      (node (ref "U1") (pin "173") (pinfunction "GPIO91_173") (pintype "passive"))
    )
    (net (code "107") (name "unconnected-(U1F-GPIO92-Pad174)") (class "Default")
      (node (ref "U1") (pin "174") (pinfunction "GPIO92_174") (pintype "passive"))
    )
    (net (code "108") (name "unconnected-(U1F-GPIO93-Pad175)") (class "Default")
      (node (ref "U1") (pin "175") (pinfunction "GPIO93_175") (pintype "passive"))
    )
    (net (code "109") (name "unconnected-(U1F-GPIO94-Pad176)") (class "Default")
      (node (ref "U1") (pin "176") (pinfunction "GPIO94_176") (pintype "passive"))
    )
    (net (code "110") (name "unconnected-(U1F-GPIO99-Pad17)") (class "Default")
      (node (ref "U1") (pin "17") (pinfunction "GPIO99_17") (pintype "passive"))
    )
    (net (code "111") (name "unconnected-(U1F-GPIO133-Pad118)") (class "Default")
      (node (ref "U1") (pin "118") (pinfunction "GPIO133_118") (pintype "passive"))
    )
    (net (code "112") (name "unconnected-(U1G-VrefHIA-Pad37)") (class "Default")
      (node (ref "U1") (pin "37") (pinfunction "VrefHIA_37") (pintype "passive"))
    )
    (net (code "113") (name "unconnected-(U1G-VrefHIB-Pad35)") (class "Default")
      (node (ref "U1") (pin "35") (pinfunction "VrefHIB_35") (pintype "passive"))
    )
    (net (code "114") (name "unconnected-(U1G-VrefHIB-Pad53)") (class "Default")
      (node (ref "U1") (pin "53") (pinfunction "VrefHIB_53") (pintype "passive"))
    )
    (net (code "115") (name "unconnected-(U1G-VrefHID-Pad55)") (class "Default")
      (node (ref "U1") (pin "55") (pinfunction "VrefHID_55") (pintype "passive"))
    )
    (net (code "116") (name "unconnected-(U1G-VrefLOA-Pad33)") (class "Default")
      (node (ref "U1") (pin "33") (pinfunction "VrefLOA_33") (pintype "passive"))
    )
    (net (code "117") (name "unconnected-(U1G-VrefLOB-Pad50)") (class "Default")
      (node (ref "U1") (pin "50") (pinfunction "VrefLOB_50") (pintype "passive"))
    )
    (net (code "118") (name "unconnected-(U1G-VrefLOC-Pad32)") (class "Default")
      (node (ref "U1") (pin "32") (pinfunction "VrefLOC_32") (pintype "passive"))
    )
    (net (code "119") (name "unconnected-(U1G-VrefLOD-Pad51)") (class "Default")
      (node (ref "U1") (pin "51") (pinfunction "VrefLOD_51") (pintype "passive"))
    )
    (net (code "120") (name "unconnected-(U1H-X1-Pad123)") (class "Default")
      (node (ref "U1") (pin "123") (pinfunction "X1_123") (pintype "passive"))
    )
    (net (code "121") (name "unconnected-(U1H-X2-Pad121)") (class "Default")
      (node (ref "U1") (pin "121") (pinfunction "X2_121") (pintype "passive"))
    )
  )
)
